# Preamp.net
KiCad netlist of a schematic drawn in Altium Designer
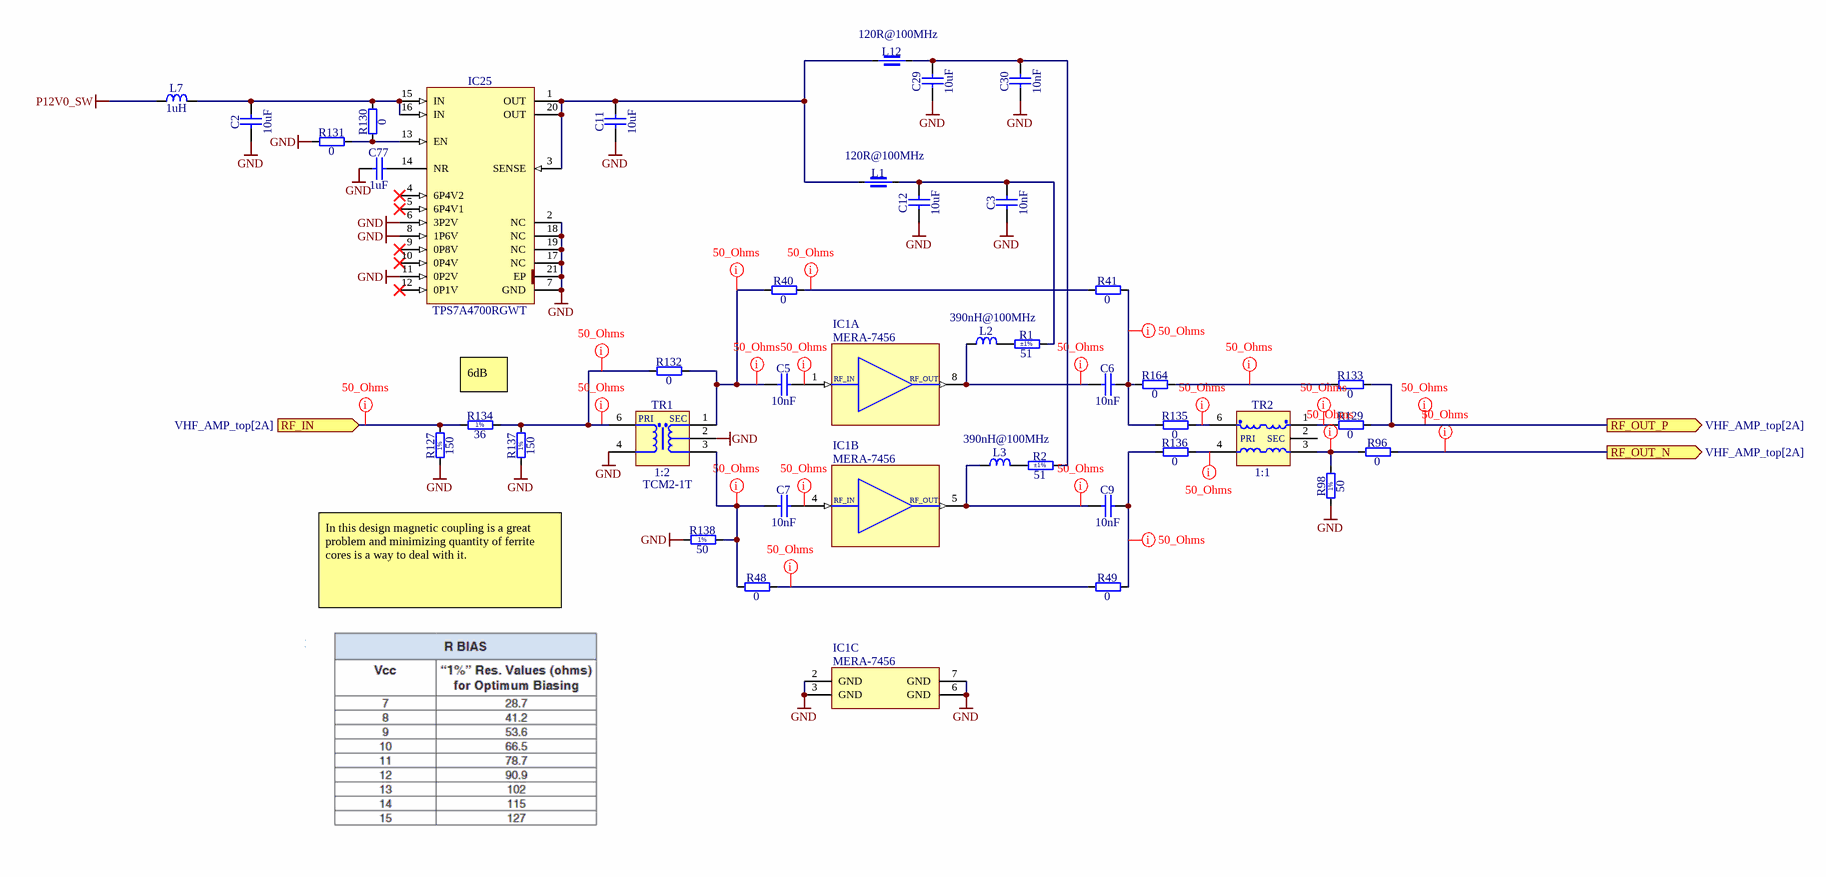
[diagram p0: Preamp.SchDoc]

(export (version "E")
  (design (tool "Eeschema 10.0.6"))
  (components
    (comp (ref "C2")
      (value "10uF")
      (footprint "CAPC3216X140N")
      (description "Non-polarised capacitor")
      (fields
        (field (name "PART NUMBER") "CC1206_10UF_10V_10%_X7R")
        (field (name "VOLTAGE") "10V")
        (field (name "AUTHOR") "CERN DEM JLC")
      )
      (libsource (lib "Capacitors") (part "Capacitor - non polarized"))
    )
    (comp (ref "C3")
      (value "10nF")
      (footprint "CAPC1005X55N")
      (description "Non-polarised capacitor")
      (fields
        (field (name "PART NUMBER") "CC0402_10NF_16V_10%_X7R")
        (field (name "VOLTAGE") "16V")
        (field (name "AUTHOR") "CERN DEM JLC")
      )
      (libsource (lib "Capacitors") (part "Capacitor - non polarized"))
    )
    (comp (ref "C5")
      (value "10nF")
      (footprint "CAPC1608X87N")
      (description "Non-polarised capacitor")
      (fields
        (field (name "PART NUMBER") "CC0603_10NF_50V_10%_X7R")
        (field (name "VOLTAGE") "50V")
        (field (name "AUTHOR") "CERN DEM JLC")
      )
      (libsource (lib "Capacitors") (part "Capacitor - non polarized"))
    )
    (comp (ref "C6")
      (value "10nF")
      (footprint "CAPC1608X87N")
      (description "Non-polarised capacitor")
      (fields
        (field (name "PART NUMBER") "CC0603_10NF_50V_10%_X7R")
        (field (name "VOLTAGE") "50V")
        (field (name "AUTHOR") "CERN DEM JLC")
      )
      (libsource (lib "Capacitors") (part "Capacitor - non polarized"))
    )
    (comp (ref "C7")
      (value "10nF")
      (footprint "CAPC1608X87N")
      (description "Non-polarised capacitor")
      (fields
        (field (name "PART NUMBER") "CC0603_10NF_50V_10%_X7R")
        (field (name "VOLTAGE") "50V")
        (field (name "AUTHOR") "CERN DEM JLC")
      )
      (libsource (lib "Capacitors") (part "Capacitor - non polarized"))
    )
    (comp (ref "C9")
      (value "10nF")
      (footprint "CAPC1608X87N")
      (description "Non-polarised capacitor")
      (fields
        (field (name "PART NUMBER") "CC0603_10NF_50V_10%_X7R")
        (field (name "VOLTAGE") "50V")
        (field (name "AUTHOR") "CERN DEM JLC")
      )
      (libsource (lib "Capacitors") (part "Capacitor - non polarized"))
    )
    (comp (ref "C11")
      (value "10uF")
      (footprint "CAPC3216X140N")
      (description "Non-polarised capacitor")
      (fields
        (field (name "PART NUMBER") "CC1206_10UF_10V_10%_X7R")
        (field (name "VOLTAGE") "10V")
        (field (name "AUTHOR") "CERN DEM JLC")
      )
      (libsource (lib "Capacitors") (part "Capacitor - non polarized"))
    )
    (comp (ref "C12")
      (value "10uF")
      (footprint "CAPC3216X140N")
      (description "Non-polarised capacitor")
      (fields
        (field (name "PART NUMBER") "CC1206_10UF_10V_10%_X7R")
        (field (name "VOLTAGE") "10V")
        (field (name "AUTHOR") "CERN DEM JLC")
      )
      (libsource (lib "Capacitors") (part "Capacitor - non polarized"))
    )
    (comp (ref "C29")
      (value "10uF")
      (footprint "CAPC3216X140N")
      (description "Non-polarised capacitor")
      (fields
        (field (name "PART NUMBER") "CC1206_10UF_10V_10%_X7R")
        (field (name "VOLTAGE") "10V")
        (field (name "AUTHOR") "CERN DEM JLC")
      )
      (libsource (lib "Capacitors") (part "Capacitor - non polarized"))
    )
    (comp (ref "C30")
      (value "10nF")
      (footprint "CAPC1005X55N")
      (description "Non-polarised capacitor")
      (fields
        (field (name "PART NUMBER") "CC0402_10NF_16V_10%_X7R")
        (field (name "VOLTAGE") "16V")
        (field (name "AUTHOR") "CERN DEM JLC")
      )
      (libsource (lib "Capacitors") (part "Capacitor - non polarized"))
    )
    (comp (ref "C77")
      (value "1uF")
      (footprint "CAPC1608X87N")
      (description "Non-polarised capacitor")
      (fields
        (field (name "PART NUMBER") "CC0603_1UF_16V_10%_X7R")
        (field (name "VOLTAGE") "16V")
        (field (name "AUTHOR") "CERN DEM JLC")
      )
      (libsource (lib "Capacitors") (part "Capacitor - non polarized"))
    )
    (comp (ref "IC1")
      (value "MERA-7456")
      (footprint "MINI-CIRCUITS_DL1020")
      (description "Dual Differential Inputs and  Complementary TTL outputs")
      (fields (field (name "MANUFACTURER") "MINI-CIRCUITS") (field (name "AUTHOR") "CERN DEM HF"))
      (libsource (lib "VHF_AMP_lib") (part "MERA-7456"))
    )
    (comp (ref "IC25")
      (value "TPS7A4700RGWT")
      (footprint "QFN65P500X500X100-21N-S325")
      (description "Low Noise (3uVrms), 1A, High Voltage Low-Dropout Linear Regulator")
      (fields
        (field (name "MANUFACTURER") "TEXAS INSTRUMENTS")
        (field (name "MANUFACTURER PART NUMBER") "TPS7A4700RGW")
        (field (name "AUTHOR") "CERN DEM JLC")
      )
      (libsource (lib "ICs And Semiconductors") (part "TPS7A4700RGW"))
    )
    (comp (ref "L1")
      (value "120R@100MHz")
      (footprint "INDC1005X55N")
      (fields
        (field (name "PART NUMBER") "IND0402_MURATA_BLM15PX121SN1D")
        (field (name "POWER") "2A")
        (field (name "TOLERANCE") "±25%")
        (field (name "AUTHOR") "CERN DEM JMW")
      )
      (libsource (lib "Inductors & Transformers") (part "Ferrite Bead"))
    )
    (comp (ref "L2")
      (value "390nH@100MHz")
      (footprint "IND_COILCRAFT_0805HP")
      (description "Inductor")
      (fields
        (field (name "PART NUMBER") "IND0805_COILCRAFT_0805HP-391XGR")
        (field (name "POWER") "330mA")
        (field (name "AUTHOR") "CERN DEM JLC")
      )
      (libsource (lib "Inductors & Transformers") (part "Inductor"))
    )
    (comp (ref "L3")
      (value "390nH@100MHz")
      (footprint "IND_COILCRAFT_0805HP")
      (description "Inductor")
      (fields
        (field (name "PART NUMBER") "IND0805_COILCRAFT_0805HP-391XGR")
        (field (name "POWER") "330mA")
        (field (name "AUTHOR") "CERN DEM JLC")
      )
      (libsource (lib "Inductors & Transformers") (part "Inductor"))
    )
    (comp (ref "L7")
      (value "1uH")
      (footprint "INDC2620X100N")
      (description "Inductor")
      (fields
        (field (name "PART NUMBER") "IND1008_1UH_20%_WURTH_74479787210B")
        (field (name "POWER") "1.95A")
        (field (name "AUTHOR") "CERN DEM JLC")
      )
      (libsource (lib "Inductors & Transformers") (part "Inductor"))
    )
    (comp (ref "L12")
      (value "120R@100MHz")
      (footprint "INDC1005X55N")
      (fields
        (field (name "PART NUMBER") "IND0402_MURATA_BLM15PX121SN1D")
        (field (name "POWER") "2A")
        (field (name "TOLERANCE") "±25%")
        (field (name "AUTHOR") "CERN DEM JMW")
      )
      (libsource (lib "Inductors & Transformers") (part "Ferrite Bead"))
    )
    (comp (ref "R1")
      (value "51")
      (footprint "RESC5025X70N")
      (description "Resistor - 1%")
      (fields
        (field (name "TOLERANCE") "±1%")
        (field (name "PART NUMBER") "R2010_51R_1%_1W_100PPM_BOURNS_CRM")
        (field (name "POWER") "1W")
        (field (name "AUTHOR") "CERN DEM JLC")
      )
      (libsource (lib "") (part "Resistor - 1%_1"))
    )
    (comp (ref "R2")
      (value "51")
      (footprint "RESC5025X70N")
      (description "Resistor - 1%")
      (fields
        (field (name "TOLERANCE") "±1%")
        (field (name "PART NUMBER") "R2010_51R_1%_1W_100PPM_BOURNS_CRM")
        (field (name "POWER") "1W")
        (field (name "AUTHOR") "CERN DEM JLC")
      )
      (libsource (lib "") (part "Resistor - 1%_1"))
    )
    (comp (ref "R40")
      (value "0")
      (footprint "RESC1608X55N")
      (description "Resistor")
      (fields
        (field (name "PART NUMBER") "R0603_0R_JUMPER")
        (field (name "MANUFACTURER") "GENERIC")
        (field (name "AUTHOR") "CERN DEM JLC")
      )
      (libsource (lib "Resistors") (part "Resistor"))
    )
    (comp (ref "R41")
      (value "0")
      (footprint "RESC1608X55N")
      (description "Resistor")
      (fields
        (field (name "PART NUMBER") "R0603_0R_JUMPER")
        (field (name "MANUFACTURER") "GENERIC")
        (field (name "AUTHOR") "CERN DEM JLC")
      )
      (libsource (lib "Resistors") (part "Resistor"))
    )
    (comp (ref "R48")
      (value "0")
      (footprint "RESC1608X55N")
      (description "Resistor")
      (fields
        (field (name "PART NUMBER") "R0603_0R_JUMPER")
        (field (name "MANUFACTURER") "GENERIC")
        (field (name "AUTHOR") "CERN DEM JLC")
      )
      (libsource (lib "Resistors") (part "Resistor"))
    )
    (comp (ref "R49")
      (value "0")
      (footprint "RESC1608X55N")
      (description "Resistor")
      (fields
        (field (name "PART NUMBER") "R0603_0R_JUMPER")
        (field (name "MANUFACTURER") "GENERIC")
        (field (name "AUTHOR") "CERN DEM JLC")
      )
      (libsource (lib "Resistors") (part "Resistor"))
    )
    (comp (ref "R96")
      (value "0")
      (footprint "RESC1608X55N")
      (description "Resistor")
      (fields
        (field (name "PART NUMBER") "R0603_0R_JUMPER")
        (field (name "MANUFACTURER") "GENERIC")
        (field (name "AUTHOR") "CERN DEM JLC")
      )
      (libsource (lib "Resistors") (part "Resistor"))
    )
    (comp (ref "R98")
      (value "50")
      (footprint "RESC1608X55N")
      (description "Resistor - 1%")
      (fields
        (field (name "PART NUMBER") "R0603_50R_1%_0.1W_100PPM")
        (field (name "POWER") "0.1W")
        (field (name "AUTHOR") "CERN DEM MR")
      )
      (libsource (lib "Resistors") (part "Resistor - 1%"))
    )
    (comp (ref "R127")
      (value "150")
      (footprint "RESC1608X55N")
      (description "Resistor - 1%")
      (fields
        (field (name "PART NUMBER") "R0603_150R_1%_0.1W_100PPM")
        (field (name "POWER") "0.1W")
        (field (name "AUTHOR") "CERN DEM JLC")
      )
      (libsource (lib "Resistors") (part "Resistor - 1%"))
    )
    (comp (ref "R129")
      (value "0")
      (footprint "RESC1608X55N")
      (description "Resistor")
      (fields
        (field (name "PART NUMBER") "R0603_0R_JUMPER")
        (field (name "MANUFACTURER") "GENERIC")
        (field (name "AUTHOR") "CERN DEM JLC")
      )
      (libsource (lib "Resistors") (part "Resistor"))
    )
    (comp (ref "R130")
      (value "0")
      (footprint "RESC1608X55N")
      (description "Resistor")
      (fields
        (field (name "PART NUMBER") "R0603_0R_JUMPER")
        (field (name "MANUFACTURER") "GENERIC")
        (field (name "AUTHOR") "CERN DEM JLC")
      )
      (libsource (lib "Resistors") (part "Resistor"))
    )
    (comp (ref "R131")
      (value "0")
      (footprint "RESC1608X55N")
      (description "Resistor")
      (fields
        (field (name "PART NUMBER") "R0603_0R_JUMPER")
        (field (name "MANUFACTURER") "GENERIC")
        (field (name "AUTHOR") "CERN DEM JLC")
      )
      (libsource (lib "Resistors") (part "Resistor"))
    )
    (comp (ref "R132")
      (value "0")
      (footprint "RESC1608X55N")
      (description "Resistor")
      (fields
        (field (name "PART NUMBER") "R0603_0R_JUMPER")
        (field (name "MANUFACTURER") "GENERIC")
        (field (name "AUTHOR") "CERN DEM JLC")
      )
      (libsource (lib "Resistors") (part "Resistor"))
    )
    (comp (ref "R133")
      (value "0")
      (footprint "RESC1608X55N")
      (description "Resistor")
      (fields
        (field (name "PART NUMBER") "R0603_0R_JUMPER")
        (field (name "MANUFACTURER") "GENERIC")
        (field (name "AUTHOR") "CERN DEM JLC")
      )
      (libsource (lib "Resistors") (part "Resistor"))
    )
    (comp (ref "R134")
      (value "36")
      (footprint "RESC1608X55N")
      (description "Resistor - 1%")
      (fields
        (field (name "PART NUMBER") "R0603_36R_1%_0.1W_100PPM")
        (field (name "MANUFACTURER") "GENERIC")
        (field (name "AUTHOR") "CERN DEM JLC")
      )
      (libsource (lib "Resistors") (part "Resistor - 1%"))
    )
    (comp (ref "R135")
      (value "0")
      (footprint "RESC1608X55N")
      (description "Resistor")
      (fields
        (field (name "PART NUMBER") "R0603_0R_JUMPER")
        (field (name "MANUFACTURER") "GENERIC")
        (field (name "AUTHOR") "CERN DEM JLC")
      )
      (libsource (lib "Resistors") (part "Resistor"))
    )
    (comp (ref "R136")
      (value "0")
      (footprint "RESC1608X55N")
      (description "Resistor")
      (fields
        (field (name "PART NUMBER") "R0603_0R_JUMPER")
        (field (name "MANUFACTURER") "GENERIC")
        (field (name "AUTHOR") "CERN DEM JLC")
      )
      (libsource (lib "Resistors") (part "Resistor"))
    )
    (comp (ref "R137")
      (value "150")
      (footprint "RESC1608X55N")
      (description "Resistor - 1%")
      (fields
        (field (name "PART NUMBER") "R0603_150R_1%_0.1W_100PPM")
        (field (name "POWER") "0.1W")
        (field (name "AUTHOR") "CERN DEM JLC")
      )
      (libsource (lib "Resistors") (part "Resistor - 1%"))
    )
    (comp (ref "R138")
      (value "50")
      (footprint "RESC1608X55N")
      (description "Resistor - 1%")
      (fields
        (field (name "PART NUMBER") "R0603_50R_1%_0.1W_100PPM")
        (field (name "MANUFACTURER") "GENERIC")
        (field (name "AUTHOR") "CERN DEM MR")
      )
      (libsource (lib "Resistors") (part "Resistor - 1%"))
    )
    (comp (ref "R164")
      (value "0")
      (footprint "RESC1608X55N")
      (description "Resistor")
      (fields
        (field (name "PART NUMBER") "R0603_0R_JUMPER")
        (field (name "MANUFACTURER") "GENERIC")
        (field (name "AUTHOR") "CERN DEM JLC")
      )
      (libsource (lib "Resistors") (part "Resistor"))
    )
    (comp (ref "TR1")
      (value "1:2")
      (footprint "XFMR_MINI-CIRCUITS_DB714")
      (description "50 Ohms 3 to 300MHz RF Transformer")
      (fields
        (field (name "PART NUMBER") "XFMR_MINI-CIRCUITS_TCM2-1T")
        (field (name "POWER") "0.25W")
        (field (name "MANUFACTURER PART NUMBER") "TCM2-1T")
        (field (name "AUTHOR") "CERN DEM HF")
      )
      (libsource (lib "Inductors & Transformers") (part "XFMR_MINI-CIRCUITS_TCM2-1T"))
    )
    (comp (ref "TR2")
      (value "1:1")
      (footprint "XFMR_MINI-CIRCUITS_AT224")
      (description "50 Ohms 4.5 To 3000MHz RF Transformers")
      (fields
        (field (name "PART NUMBER") "XFMR_MINI-CIRCUITS_TC1-1-13M+")
        (field (name "MANUFACTURER") "MINI-CIRCUITS")
        (field (name "AUTHOR") "CERN DEM JLC")
      )
      (libsource (lib "Inductors & Transformers") (part "XFMR_MINI-CIRCUITS_TC1-1-13M+"))
    )
  )
  (nets
    (net (code "1") (name "/RF_IN") (class "Default")
      (node (ref "R127") (pin "2") (pinfunction "2_2") (pintype "passive"))
      (node (ref "R134") (pin "1") (pinfunction "1_1") (pintype "passive"))
    )
    (net (code "2") (name "/RF_OUT_N") (class "Default")
      (node (ref "R96") (pin "2") (pinfunction "2_2") (pintype "passive"))
    )
    (net (code "3") (name "/RF_OUT_P") (class "Default")
      (node (ref "R129") (pin "2") (pinfunction "2_2") (pintype "passive"))
      (node (ref "R133") (pin "2") (pinfunction "2_2") (pintype "passive"))
    )
    (net (code "4") (name "GND") (class "Default")
      (node (ref "C11") (pin "1") (pinfunction "1_1") (pintype "passive"))
      (node (ref "C12") (pin "1") (pinfunction "1_1") (pintype "passive"))
      (node (ref "C2") (pin "1") (pinfunction "1_1") (pintype "passive"))
      (node (ref "C29") (pin "1") (pinfunction "1_1") (pintype "passive"))
      (node (ref "C3") (pin "1") (pinfunction "1_1") (pintype "passive"))
      (node (ref "C30") (pin "1") (pinfunction "1_1") (pintype "passive"))
      (node (ref "C77") (pin "1") (pinfunction "1_1") (pintype "passive"))
      (node (ref "IC1") (pin "2") (pinfunction "GND_2") (pintype "passive"))
      (node (ref "IC1") (pin "3") (pinfunction "GND_3") (pintype "passive"))
      (node (ref "IC1") (pin "6") (pinfunction "GND_6") (pintype "passive"))
      (node (ref "IC1") (pin "7") (pinfunction "GND_7") (pintype "passive"))
      (node (ref "IC25") (pin "11") (pinfunction "0P2V_11") (pintype "input"))
      (node (ref "IC25") (pin "17") (pinfunction "NC_17") (pintype "passive"))
      (node (ref "IC25") (pin "18") (pinfunction "NC_18") (pintype "passive"))
      (node (ref "IC25") (pin "19") (pinfunction "NC_19") (pintype "passive"))
      (node (ref "IC25") (pin "2") (pinfunction "NC_2") (pintype "passive"))
      (node (ref "IC25") (pin "21") (pinfunction "EP_21") (pintype "power_in"))
      (node (ref "IC25") (pin "6") (pinfunction "3P2V_6") (pintype "input"))
      (node (ref "IC25") (pin "7") (pinfunction "GND_7") (pintype "power_in"))
      (node (ref "IC25") (pin "8") (pinfunction "1P6V_8") (pintype "input"))
      (node (ref "R127") (pin "1") (pinfunction "1_1") (pintype "passive"))
      (node (ref "R131") (pin "1") (pinfunction "1_1") (pintype "passive"))
      (node (ref "R137") (pin "1") (pinfunction "1_1") (pintype "passive"))
      (node (ref "R138") (pin "1") (pinfunction "1_1") (pintype "passive"))
      (node (ref "R98") (pin "1") (pinfunction "1_1") (pintype "passive"))
      (node (ref "TR1") (pin "2") (pinfunction "NU_2") (pintype "passive"))
      (node (ref "TR1") (pin "4") (pinfunction "P_4") (pintype "passive"))
    )
    (net (code "5") (name "Net-(C2-Pad2)") (class "Default")
      (node (ref "C2") (pin "2") (pinfunction "2_2") (pintype "passive"))
      (node (ref "IC25") (pin "15") (pinfunction "IN_15") (pintype "input"))
      (node (ref "IC25") (pin "16") (pinfunction "IN_16") (pintype "input"))
      (node (ref "L7") (pin "2") (pinfunction "2_2") (pintype "passive"))
      (node (ref "R130") (pin "2") (pinfunction "2_2") (pintype "passive"))
    )
    (net (code "6") (name "Net-(C6-Pad2)") (class "Default")
      (node (ref "C6") (pin "2") (pinfunction "2_2") (pintype "passive"))
      (node (ref "R135") (pin "1") (pinfunction "1_1") (pintype "passive"))
      (node (ref "R164") (pin "1") (pinfunction "1_1") (pintype "passive"))
      (node (ref "R41") (pin "2") (pinfunction "2_2") (pintype "passive"))
    )
    (net (code "7") (name "Net-(C9-Pad2)") (class "Default")
      (node (ref "C9") (pin "2") (pinfunction "2_2") (pintype "passive"))
      (node (ref "R136") (pin "1") (pinfunction "1_1") (pintype "passive"))
      (node (ref "R49") (pin "2") (pinfunction "2_2") (pintype "passive"))
    )
    (net (code "8") (name "Net-(C12-Pad2)") (class "Default")
      (node (ref "C12") (pin "2") (pinfunction "2_2") (pintype "passive"))
      (node (ref "C3") (pin "2") (pinfunction "2_2") (pintype "passive"))
      (node (ref "L1") (pin "2") (pinfunction "2_2") (pintype "passive"))
      (node (ref "R1") (pin "2") (pinfunction "2_2") (pintype "passive"))
    )
    (net (code "9") (name "Net-(C29-Pad2)") (class "Default")
      (node (ref "C29") (pin "2") (pinfunction "2_2") (pintype "passive"))
      (node (ref "C30") (pin "2") (pinfunction "2_2") (pintype "passive"))
      (node (ref "L12") (pin "2") (pinfunction "2_2") (pintype "passive"))
      (node (ref "R2") (pin "2") (pinfunction "2_2") (pintype "passive"))
    )
    (net (code "10") (name "Net-(IC1A-RF-IN,_A1)") (class "Default")
      (node (ref "C5") (pin "2") (pinfunction "2_2") (pintype "passive"))
      (node (ref "IC1") (pin "1") (pinfunction "RF-IN,_A1_1") (pintype "input"))
    )
    (net (code "11") (name "Net-(IC1A-RF-OUT_and_DC-IN,_A1)") (class "Default")
      (node (ref "C6") (pin "1") (pinfunction "1_1") (pintype "passive"))
      (node (ref "IC1") (pin "8") (pinfunction "RF-OUT_and_DC-IN,_A1_8") (pintype "output"))
      (node (ref "L2") (pin "1") (pinfunction "1_1") (pintype "passive"))
    )
    (net (code "12") (name "Net-(IC1B-RF-OUT_and_DC-IN,_A2)") (class "Default")
      (node (ref "C9") (pin "1") (pinfunction "1_1") (pintype "passive"))
      (node (ref "IC1") (pin "5") (pinfunction "RF-OUT_and_DC-IN,_A2_5") (pintype "output"))
      (node (ref "L3") (pin "1") (pinfunction "1_1") (pintype "passive"))
    )
    (net (code "13") (name "Net-(IC1B-RF_IN,_A2)") (class "Default")
      (node (ref "C7") (pin "2") (pinfunction "2_2") (pintype "passive"))
      (node (ref "IC1") (pin "4") (pinfunction "RF_IN,_A2_4") (pintype "input"))
    )
    (net (code "14") (name "Net-(IC25-EN)") (class "Default")
      (node (ref "IC25") (pin "13") (pinfunction "EN_13") (pintype "input"))
      (node (ref "R130") (pin "1") (pinfunction "1_1") (pintype "passive"))
      (node (ref "R131") (pin "2") (pinfunction "2_2") (pintype "passive"))
    )
    (net (code "15") (name "Net-(IC25-NR)") (class "Default")
      (node (ref "C77") (pin "2") (pinfunction "2_2") (pintype "passive"))
      (node (ref "IC25") (pin "14") (pinfunction "NR_14") (pintype "passive"))
    )
    (net (code "16") (name "Net-(IC25-SENSE)") (class "Default")
      (node (ref "C11") (pin "2") (pinfunction "2_2") (pintype "passive"))
      (node (ref "IC25") (pin "1") (pinfunction "OUT_1") (pintype "power_in"))
      (node (ref "IC25") (pin "20") (pinfunction "OUT_20") (pintype "power_in"))
      (node (ref "IC25") (pin "3") (pinfunction "SENSE_3") (pintype "input"))
      (node (ref "L1") (pin "1") (pinfunction "1_1") (pintype "passive"))
      (node (ref "L12") (pin "1") (pinfunction "1_1") (pintype "passive"))
    )
    (net (code "17") (name "Net-(L2-Pad2)") (class "Default")
      (node (ref "L2") (pin "2") (pinfunction "2_2") (pintype "passive"))
      (node (ref "R1") (pin "1") (pinfunction "1_1") (pintype "passive"))
    )
    (net (code "18") (name "Net-(L3-Pad2)") (class "Default")
      (node (ref "L3") (pin "2") (pinfunction "2_2") (pintype "passive"))
      (node (ref "R2") (pin "1") (pinfunction "1_1") (pintype "passive"))
    )
    (net (code "19") (name "Net-(R40-Pad2)") (class "Default")
      (node (ref "R40") (pin "2") (pinfunction "2_2") (pintype "passive"))
      (node (ref "R41") (pin "1") (pinfunction "1_1") (pintype "passive"))
    )
    (net (code "20") (name "Net-(R48-Pad2)") (class "Default")
      (node (ref "R48") (pin "2") (pinfunction "2_2") (pintype "passive"))
      (node (ref "R49") (pin "1") (pinfunction "1_1") (pintype "passive"))
    )
    (net (code "21") (name "Net-(R133-Pad1)") (class "Default")
      (node (ref "R133") (pin "1") (pinfunction "1_1") (pintype "passive"))
      (node (ref "R164") (pin "2") (pinfunction "2_2") (pintype "passive"))
    )
    (net (code "22") (name "Net-(TR1-PDOT)") (class "Default")
      (node (ref "R132") (pin "1") (pinfunction "1_1") (pintype "passive"))
      (node (ref "R134") (pin "2") (pinfunction "2_2") (pintype "passive"))
      (node (ref "R137") (pin "2") (pinfunction "2_2") (pintype "passive"))
      (node (ref "TR1") (pin "6") (pinfunction "PDOT_6") (pintype "passive"))
    )
    (net (code "23") (name "Net-(TR1-S)") (class "Default")
      (node (ref "C7") (pin "1") (pinfunction "1_1") (pintype "passive"))
      (node (ref "R138") (pin "2") (pinfunction "2_2") (pintype "passive"))
      (node (ref "R48") (pin "1") (pinfunction "1_1") (pintype "passive"))
      (node (ref "TR1") (pin "3") (pinfunction "S_3") (pintype "passive"))
    )
    (net (code "24") (name "Net-(TR1-SDOT)") (class "Default")
      (node (ref "C5") (pin "1") (pinfunction "1_1") (pintype "passive"))
      (node (ref "R132") (pin "2") (pinfunction "2_2") (pintype "passive"))
      (node (ref "R40") (pin "1") (pinfunction "1_1") (pintype "passive"))
      (node (ref "TR1") (pin "1") (pinfunction "SDOT_1") (pintype "passive"))
    )
    (net (code "25") (name "Net-(TR2-P)") (class "Default")
      (node (ref "R136") (pin "2") (pinfunction "2_2") (pintype "passive"))
      (node (ref "TR2") (pin "4") (pinfunction "P_4") (pintype "passive"))
    )
    (net (code "26") (name "Net-(TR2-PDOT)") (class "Default")
      (node (ref "R135") (pin "2") (pinfunction "2_2") (pintype "passive"))
      (node (ref "TR2") (pin "6") (pinfunction "PDOT_6") (pintype "passive"))
    )
    (net (code "27") (name "Net-(TR2-S)") (class "Default")
      (node (ref "R96") (pin "1") (pinfunction "1_1") (pintype "passive"))
      (node (ref "R98") (pin "2") (pinfunction "2_2") (pintype "passive"))
      (node (ref "TR2") (pin "3") (pinfunction "S_3") (pintype "passive"))
    )
    (net (code "28") (name "Net-(TR2-SDOT)") (class "Default")
      (node (ref "R129") (pin "1") (pinfunction "1_1") (pintype "passive"))
      (node (ref "TR2") (pin "1") (pinfunction "SDOT_1") (pintype "passive"))
    )
    (net (code "29") (name "P12V0_SW") (class "Default")
      (node (ref "L7") (pin "1") (pinfunction "1_1") (pintype "passive"))
    )
    (net (code "30") (name "unconnected-(IC25-0P1V-Pad12)") (class "Default")
      (node (ref "IC25") (pin "12") (pinfunction "0P1V_12") (pintype "input+no_connect"))
    )
    (net (code "31") (name "unconnected-(IC25-0P4V-Pad10)") (class "Default")
      (node (ref "IC25") (pin "10") (pinfunction "0P4V_10") (pintype "input+no_connect"))
    )
    (net (code "32") (name "unconnected-(IC25-0P8V-Pad9)") (class "Default")
      (node (ref "IC25") (pin "9") (pinfunction "0P8V_9") (pintype "input+no_connect"))
    )
    (net (code "33") (name "unconnected-(IC25-6P4V1-Pad5)") (class "Default")
      (node (ref "IC25") (pin "5") (pinfunction "6P4V1_5") (pintype "input+no_connect"))
    )
    (net (code "34") (name "unconnected-(IC25-6P4V2-Pad4)") (class "Default")
      (node (ref "IC25") (pin "4") (pinfunction "6P4V2_4") (pintype "input+no_connect"))
    )
    (net (code "35") (name "unconnected-(TR2-NC-Pad2)") (class "Default")
      (node (ref "TR2") (pin "2") (pinfunction "NC_2") (pintype "passive"))
    )
  )
)
